# Mono_Slider.net
KiCad netlist of a schematic drawn in EAGLE
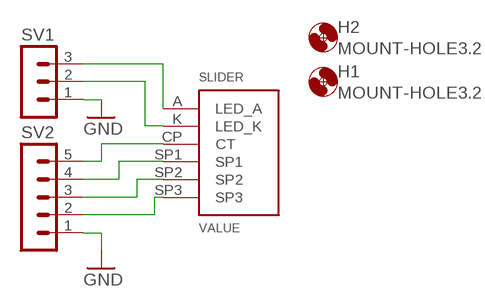
[diagram p0: schematic, sheet 1]

(export (version "E")
  (design (tool "Eeschema 10.0.6"))
  (components
    (comp (ref "H1")
      (value "MOUNT-HOLE3.2")
      (footprint "eagle-import:3,2")
      (libsource (lib "eagle-import") (part "MOUNT-HOLE3.2"))
    )
    (comp (ref "H2")
      (value "MOUNT-HOLE3.2")
      (footprint "eagle-import:3,2")
      (libsource (lib "eagle-import") (part "MOUNT-HOLE3.2"))
    )
    (comp (ref "SL1")
      (value "SLIDER")
      (footprint "eagle-import:SLIDER_SMALL")
      (libsource (lib "eagle-import") (part "SLIDERSLIDER_SMALL"))
    )
    (comp (ref "SV1")
      (value "MA03-1")
      (footprint "eagle-import:MA03-1")
      (libsource (lib "eagle-import") (part "MA03-1"))
    )
    (comp (ref "SV2")
      (value "MA05-1")
      (footprint "eagle-import:MA05-1")
      (libsource (lib "eagle-import") (part "MA05-1"))
    )
  )
  (nets
    (net (code "1") (name "GND") (class "Default")
      (node (ref "SV1") (pin "1") (pinfunction "1_1") (pintype "passive"))
      (node (ref "SV2") (pin "1") (pinfunction "1_1") (pintype "passive"))
    )
    (net (code "2") (name "Net-(SL1-CT)") (class "Default")
      (node (ref "SL1") (pin "CP") (pinfunction "CT_CP") (pintype "bidirectional"))
      (node (ref "SV2") (pin "5") (pinfunction "5_5") (pintype "passive"))
    )
    (net (code "3") (name "Net-(SL1-LED_A)") (class "Default")
      (node (ref "SL1") (pin "A") (pinfunction "LED_A_A") (pintype "power_in"))
      (node (ref "SV1") (pin "3") (pinfunction "3_3") (pintype "passive"))
    )
    (net (code "4") (name "Net-(SL1-LED_K)") (class "Default")
      (node (ref "SL1") (pin "K") (pinfunction "LED_K_K") (pintype "power_in"))
      (node (ref "SV1") (pin "2") (pinfunction "2_2") (pintype "passive"))
    )
    (net (code "5") (name "Net-(SL1-PadSP1)") (class "Default")
      (node (ref "SL1") (pin "SP1") (pinfunction "SP1_SP1") (pintype "bidirectional"))
      (node (ref "SV2") (pin "4") (pinfunction "4_4") (pintype "passive"))
    )
    (net (code "6") (name "Net-(SL1-PadSP2)") (class "Default")
      (node (ref "SL1") (pin "SP2") (pinfunction "SP2_SP2") (pintype "bidirectional"))
      (node (ref "SV2") (pin "3") (pinfunction "3_3") (pintype "passive"))
    )
    (net (code "7") (name "Net-(SL1-PadSP3)") (class "Default")
      (node (ref "SL1") (pin "SP3") (pinfunction "SP3_SP3") (pintype "bidirectional"))
      (node (ref "SV2") (pin "2") (pinfunction "2_2") (pintype "passive"))
    )
  )
)
